# prim_analog_in.net
KiCad netlist of a schematic drawn in Altium Designer
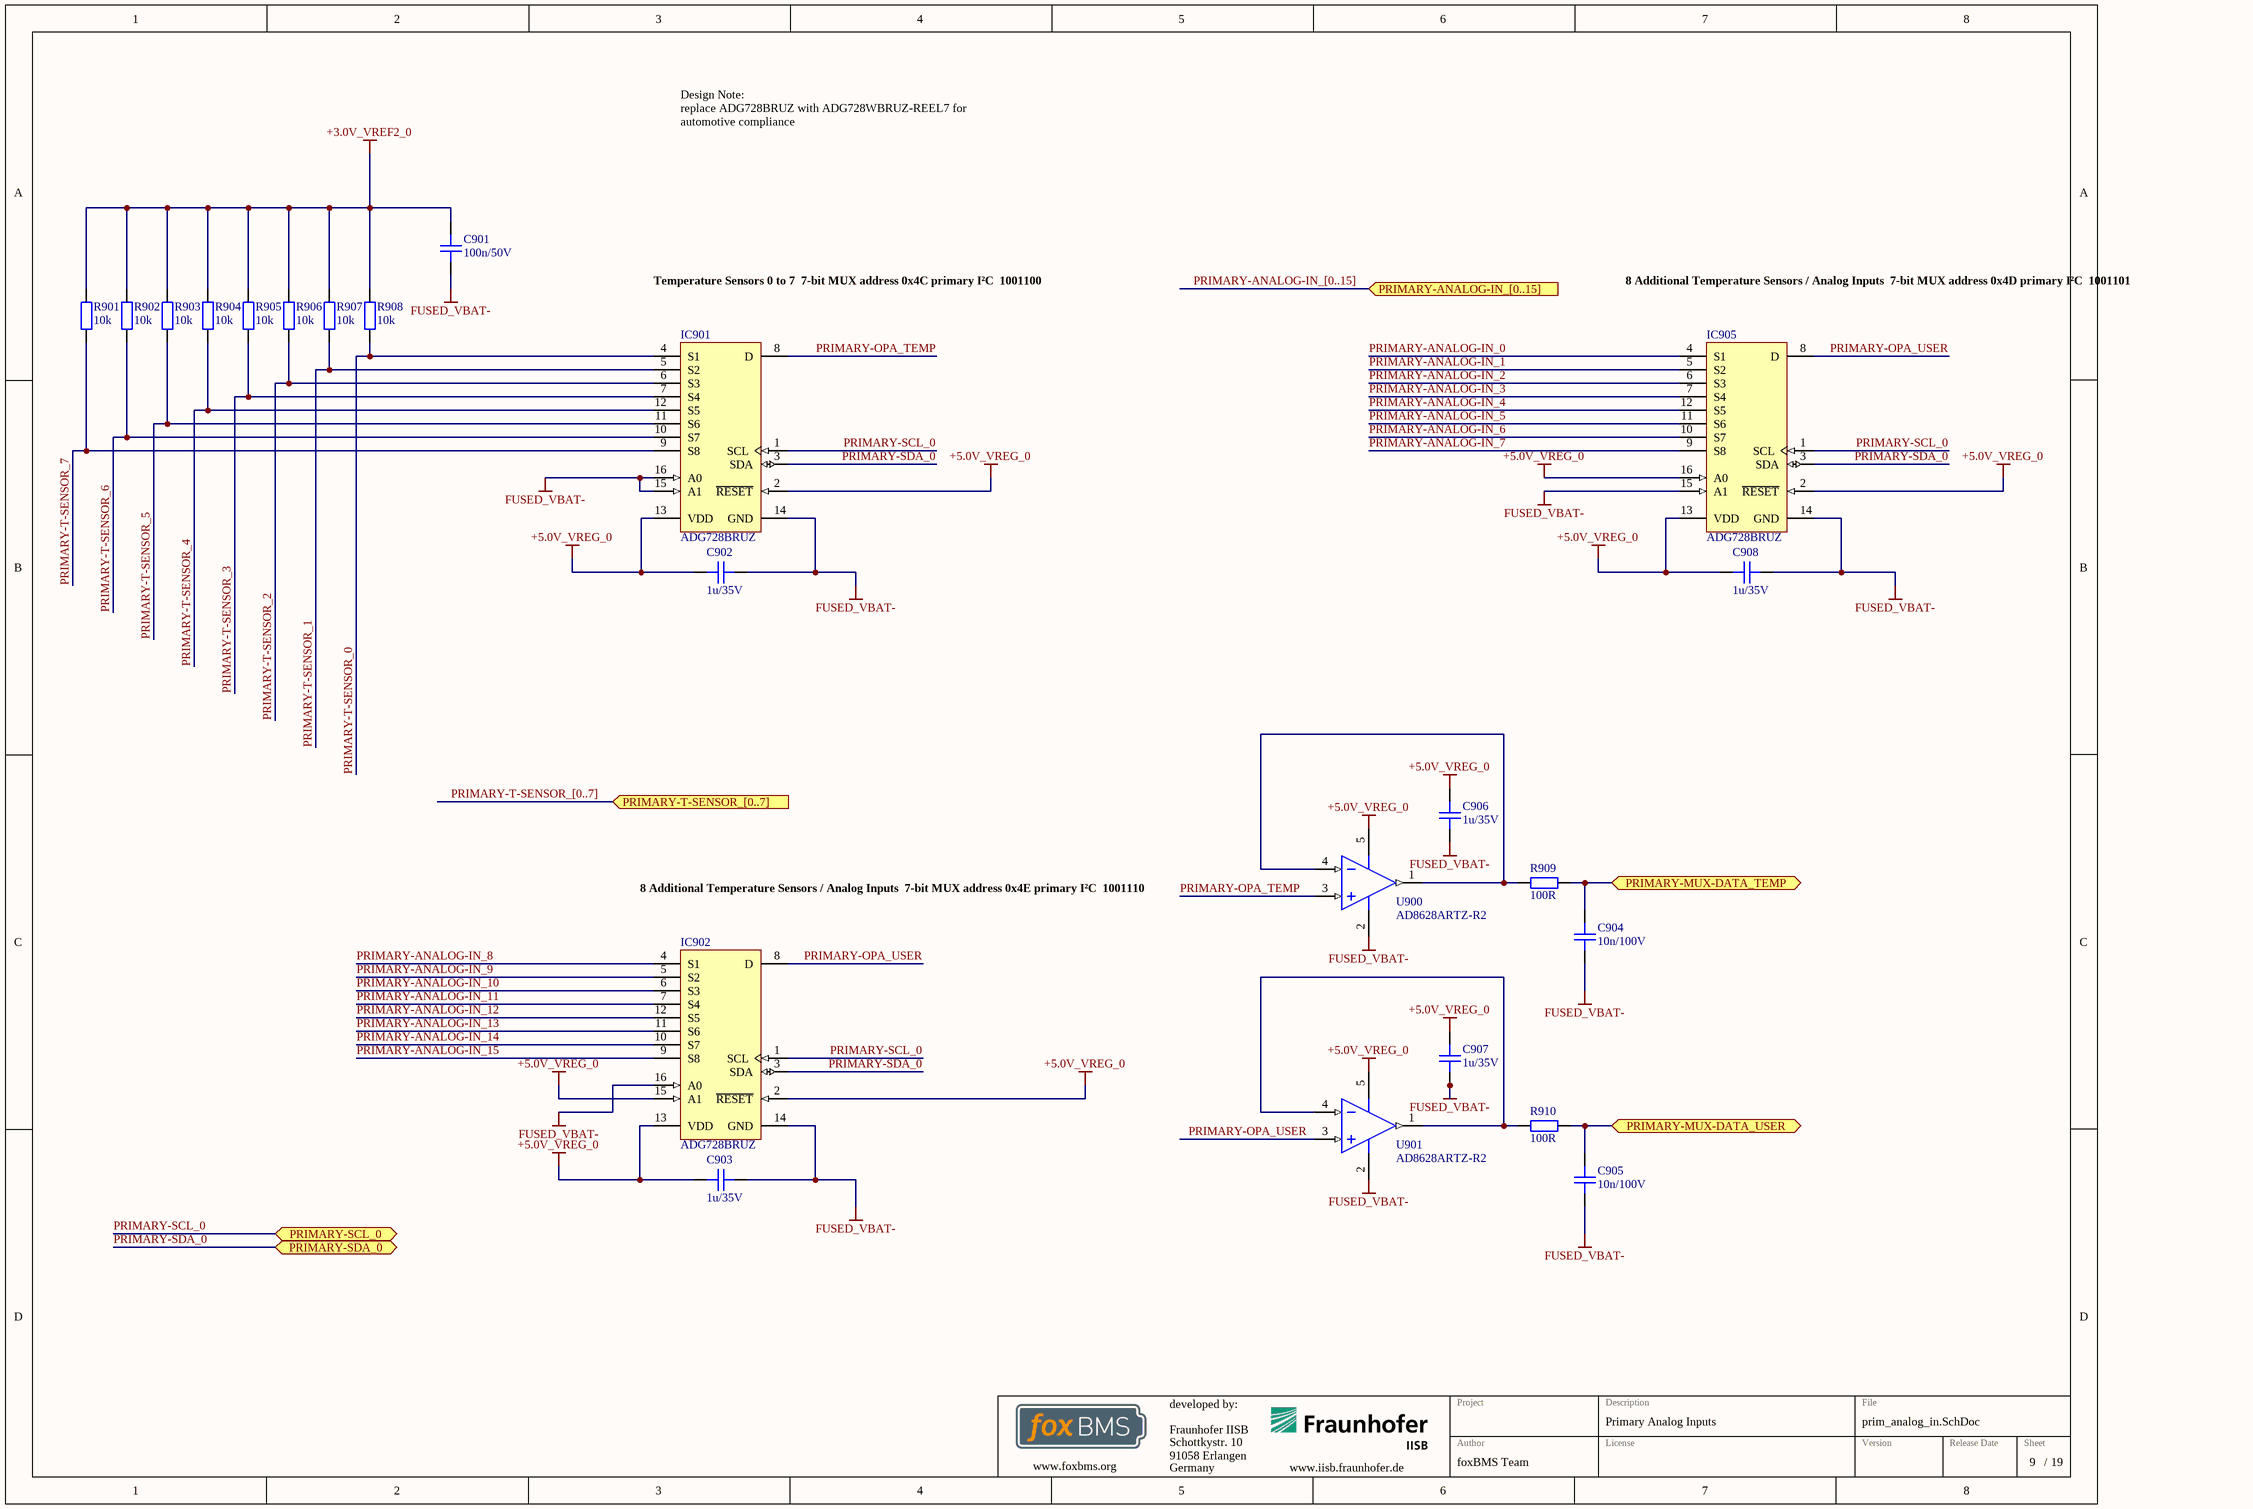
[diagram p0: prim_analog_in.SchDoc]

(export (version "E")
  (design (tool "Eeschema 10.0.6"))
  (components
    (comp (ref "C901")
      (value "100n/50V")
      (footprint "CAPC1608X08N")
      (description "MLCC")
      (fields (field (name "PART NUMBER") "gen_C_ceramic_100n_50V_X7R_0603"))
      (libsource (lib "OE750") (part "C"))
    )
    (comp (ref "C902")
      (value "1u/35V")
      (footprint "CAPC1608X08N")
      (description "MLCC")
      (fields (field (name "PART NUMBER") "gen_C_ceramic_1u_35V_X7R_0603"))
      (libsource (lib "OE750") (part "C"))
    )
    (comp (ref "C903")
      (value "1u/35V")
      (footprint "CAPC1608X08N")
      (description "MLCC")
      (fields (field (name "PART NUMBER") "gen_C_ceramic_1u_35V_X7R_0603"))
      (libsource (lib "OE750") (part "C"))
    )
    (comp (ref "C904")
      (value "10n/100V")
      (footprint "CAPC1608X08N")
      (description "MLCC")
      (fields (field (name "PART NUMBER") "gen_C_ceramic_10n_100V_X7R_0603"))
      (libsource (lib "OE750") (part "C"))
    )
    (comp (ref "C905")
      (value "10n/100V")
      (footprint "CAPC1608X08N")
      (description "MLCC")
      (fields (field (name "PART NUMBER") "gen_C_ceramic_10n_100V_X7R_0603"))
      (libsource (lib "OE750") (part "C"))
    )
    (comp (ref "C906")
      (value "1u/35V")
      (footprint "CAPC1608X08N")
      (description "MLCC")
      (fields (field (name "PART NUMBER") "gen_C_ceramic_1u_35V_X7R_0603"))
      (libsource (lib "OE750") (part "C"))
    )
    (comp (ref "C907")
      (value "1u/35V")
      (footprint "CAPC1608X08N")
      (description "MLCC")
      (fields (field (name "PART NUMBER") "gen_C_ceramic_1u_35V_X7R_0603"))
      (libsource (lib "OE750") (part "C"))
    )
    (comp (ref "C908")
      (value "1u/35V")
      (footprint "CAPC1608X08N")
      (description "MLCC")
      (fields (field (name "PART NUMBER") "gen_C_ceramic_1u_35V_X7R_0603"))
      (libsource (lib "OE750") (part "C"))
    )
    (comp (ref "IC901")
      (value "ADG728BRUZ")
      (footprint "ADI-RU-16_M")
      (fields (field (name "MANUFACTURER") "Analog Devices"))
      (libsource (lib "Altium Content Vault") (part "ADI-ADG728-RU-16"))
    )
    (comp (ref "IC902")
      (value "ADG728BRUZ")
      (footprint "ADI-RU-16_M")
      (fields (field (name "MANUFACTURER") "Analog Devices"))
      (libsource (lib "Altium Content Vault") (part "ADI-ADG728-RU-16"))
    )
    (comp (ref "IC905")
      (value "ADG728BRUZ")
      (footprint "ADI-RU-16_M")
      (fields (field (name "MANUFACTURER") "Analog Devices"))
      (libsource (lib "Altium Content Vault") (part "ADI-ADG728-RU-16"))
    )
    (comp (ref "R901")
      (value "10k")
      (footprint "RESC1608X05N")
      (description "SMD Resistor 10k 0603")
      (fields (field (name "PART NUMBER") "gen_R_10k_0603") (field (name "TOLERANCE") "1%"))
      (libsource (lib "OE750") (part "R"))
    )
    (comp (ref "R902")
      (value "10k")
      (footprint "RESC1608X05N")
      (description "SMD Resistor 10k 0603")
      (fields (field (name "PART NUMBER") "gen_R_10k_0603") (field (name "TOLERANCE") "1%"))
      (libsource (lib "OE750") (part "R"))
    )
    (comp (ref "R903")
      (value "10k")
      (footprint "RESC1608X05N")
      (description "SMD Resistor 10k 0603")
      (fields (field (name "PART NUMBER") "gen_R_10k_0603") (field (name "TOLERANCE") "1%"))
      (libsource (lib "OE750") (part "R"))
    )
    (comp (ref "R904")
      (value "10k")
      (footprint "RESC1608X05N")
      (description "SMD Resistor 10k 0603")
      (fields (field (name "PART NUMBER") "gen_R_10k_0603") (field (name "TOLERANCE") "1%"))
      (libsource (lib "OE750") (part "R"))
    )
    (comp (ref "R905")
      (value "10k")
      (footprint "RESC1608X05N")
      (description "SMD Resistor 10k 0603")
      (fields (field (name "PART NUMBER") "gen_R_10k_0603") (field (name "TOLERANCE") "1%"))
      (libsource (lib "OE750") (part "R"))
    )
    (comp (ref "R906")
      (value "10k")
      (footprint "RESC1608X05N")
      (description "SMD Resistor 10k 0603")
      (fields (field (name "PART NUMBER") "gen_R_10k_0603") (field (name "TOLERANCE") "1%"))
      (libsource (lib "OE750") (part "R"))
    )
    (comp (ref "R907")
      (value "10k")
      (footprint "RESC1608X05N")
      (description "SMD Resistor 10k 0603")
      (fields (field (name "PART NUMBER") "gen_R_10k_0603") (field (name "TOLERANCE") "1%"))
      (libsource (lib "OE750") (part "R"))
    )
    (comp (ref "R908")
      (value "10k")
      (footprint "RESC1608X05N")
      (description "SMD Resistor 10k 0603")
      (fields (field (name "PART NUMBER") "gen_R_10k_0603") (field (name "TOLERANCE") "1%"))
      (libsource (lib "OE750") (part "R"))
    )
    (comp (ref "R909")
      (value "100R")
      (footprint "RESC1608X05N")
      (description "SMD Resistor 100R 0603")
      (fields (field (name "PART NUMBER") "gen_R_100R_0603") (field (name "TOLERANCE") "1%"))
      (libsource (lib "OE750") (part "R"))
    )
    (comp (ref "R910")
      (value "100R")
      (footprint "RESC1608X05N")
      (description "SMD Resistor 100R 0603")
      (fields (field (name "PART NUMBER") "gen_R_100R_0603") (field (name "TOLERANCE") "1%"))
      (libsource (lib "OE750") (part "R"))
    )
    (comp (ref "U900")
      (value "AD8628ARTZ-R2")
      (footprint "ADI-RJ-5_M")
      (fields (field (name "MANUFACTURER") "Analog Devices") (field (name "GENERIC PART NUMBER") "AD8628"))
      (libsource (lib "Altium Content Vault") (part "ADI-ADxxxx-X-5"))
    )
    (comp (ref "U901")
      (value "AD8628ARTZ-R2")
      (footprint "ADI-RJ-5_M")
      (fields (field (name "MANUFACTURER") "Analog Devices") (field (name "GENERIC PART NUMBER") "AD8628"))
      (libsource (lib "Altium Content Vault") (part "ADI-ADxxxx-X-5"))
    )
  )
  (nets
    (net (code "1") (name "+3.0V_VREF2_0") (class "Default")
      (node (ref "C901") (pin "2") (pinfunction "2_2") (pintype "passive"))
      (node (ref "R901") (pin "2") (pinfunction "2_2") (pintype "passive"))
      (node (ref "R902") (pin "2") (pinfunction "2_2") (pintype "passive"))
      (node (ref "R903") (pin "2") (pinfunction "2_2") (pintype "passive"))
      (node (ref "R904") (pin "2") (pinfunction "2_2") (pintype "passive"))
      (node (ref "R905") (pin "2") (pinfunction "2_2") (pintype "passive"))
      (node (ref "R906") (pin "2") (pinfunction "2_2") (pintype "passive"))
      (node (ref "R907") (pin "2") (pinfunction "2_2") (pintype "passive"))
      (node (ref "R908") (pin "2") (pinfunction "2_2") (pintype "passive"))
    )
    (net (code "2") (name "+5.0V_VREG_0") (class "Default")
      (node (ref "C902") (pin "2") (pinfunction "2_2") (pintype "passive"))
      (node (ref "C903") (pin "2") (pinfunction "2_2") (pintype "passive"))
      (node (ref "C906") (pin "2") (pinfunction "2_2") (pintype "passive"))
      (node (ref "C907") (pin "2") (pinfunction "2_2") (pintype "passive"))
      (node (ref "C908") (pin "2") (pinfunction "2_2") (pintype "passive"))
      (node (ref "IC901") (pin "13") (pinfunction "VDD_13") (pintype "power_in"))
      (node (ref "IC901") (pin "2") (pinfunction "~{RESET}_2") (pintype "input"))
      (node (ref "IC902") (pin "13") (pinfunction "VDD_13") (pintype "power_in"))
      (node (ref "IC902") (pin "15") (pinfunction "A1_15") (pintype "input"))
      (node (ref "IC902") (pin "2") (pinfunction "~{RESET}_2") (pintype "input"))
      (node (ref "IC905") (pin "13") (pinfunction "VDD_13") (pintype "power_in"))
      (node (ref "IC905") (pin "16") (pinfunction "A0_16") (pintype "input"))
      (node (ref "IC905") (pin "2") (pinfunction "~{RESET}_2") (pintype "input"))
      (node (ref "U900") (pin "5") (pinfunction "+V_5") (pintype "power_in"))
      (node (ref "U901") (pin "5") (pinfunction "+V_5") (pintype "power_in"))
    )
    (net (code "3") (name "/PRIMARY-ANALOG-IN_0") (class "Default")
      (node (ref "IC905") (pin "4") (pinfunction "S1_4") (pintype "passive"))
    )
    (net (code "4") (name "/PRIMARY-ANALOG-IN_1") (class "Default")
      (node (ref "IC905") (pin "5") (pinfunction "S2_5") (pintype "passive"))
    )
    (net (code "5") (name "/PRIMARY-ANALOG-IN_2") (class "Default")
      (node (ref "IC905") (pin "6") (pinfunction "S3_6") (pintype "passive"))
    )
    (net (code "6") (name "/PRIMARY-ANALOG-IN_3") (class "Default")
      (node (ref "IC905") (pin "7") (pinfunction "S4_7") (pintype "passive"))
    )
    (net (code "7") (name "/PRIMARY-ANALOG-IN_4") (class "Default")
      (node (ref "IC905") (pin "12") (pinfunction "S5_12") (pintype "passive"))
    )
    (net (code "8") (name "/PRIMARY-ANALOG-IN_5") (class "Default")
      (node (ref "IC905") (pin "11") (pinfunction "S6_11") (pintype "passive"))
    )
    (net (code "9") (name "/PRIMARY-ANALOG-IN_6") (class "Default")
      (node (ref "IC905") (pin "10") (pinfunction "S7_10") (pintype "passive"))
    )
    (net (code "10") (name "/PRIMARY-ANALOG-IN_7") (class "Default")
      (node (ref "IC905") (pin "9") (pinfunction "S8_9") (pintype "passive"))
    )
    (net (code "11") (name "/PRIMARY-ANALOG-IN_8") (class "Default")
      (node (ref "IC902") (pin "4") (pinfunction "S1_4") (pintype "passive"))
    )
    (net (code "12") (name "/PRIMARY-ANALOG-IN_9") (class "Default")
      (node (ref "IC902") (pin "5") (pinfunction "S2_5") (pintype "passive"))
    )
    (net (code "13") (name "/PRIMARY-ANALOG-IN_10") (class "Default")
      (node (ref "IC902") (pin "6") (pinfunction "S3_6") (pintype "passive"))
    )
    (net (code "14") (name "/PRIMARY-ANALOG-IN_11") (class "Default")
      (node (ref "IC902") (pin "7") (pinfunction "S4_7") (pintype "passive"))
    )
    (net (code "15") (name "/PRIMARY-ANALOG-IN_12") (class "Default")
      (node (ref "IC902") (pin "12") (pinfunction "S5_12") (pintype "passive"))
    )
    (net (code "16") (name "/PRIMARY-ANALOG-IN_13") (class "Default")
      (node (ref "IC902") (pin "11") (pinfunction "S6_11") (pintype "passive"))
    )
    (net (code "17") (name "/PRIMARY-ANALOG-IN_14") (class "Default")
      (node (ref "IC902") (pin "10") (pinfunction "S7_10") (pintype "passive"))
    )
    (net (code "18") (name "/PRIMARY-ANALOG-IN_15") (class "Default")
      (node (ref "IC902") (pin "9") (pinfunction "S8_9") (pintype "passive"))
    )
    (net (code "20") (name "/PRIMARY-MUX-DATA_TEMP") (class "Default")
      (node (ref "C904") (pin "2") (pinfunction "2_2") (pintype "passive"))
      (node (ref "R909") (pin "2") (pinfunction "2_2") (pintype "passive"))
    )
    (net (code "21") (name "/PRIMARY-MUX-DATA_USER") (class "Default")
      (node (ref "C905") (pin "2") (pinfunction "2_2") (pintype "passive"))
      (node (ref "R910") (pin "2") (pinfunction "2_2") (pintype "passive"))
    )
    (net (code "22") (name "/PRIMARY-OPA_TEMP") (class "Default")
      (node (ref "IC901") (pin "8") (pinfunction "D_8") (pintype "passive"))
      (node (ref "U900") (pin "3") (pinfunction "+IN_3") (pintype "input"))
    )
    (net (code "23") (name "/PRIMARY-OPA_USER") (class "Default")
      (node (ref "IC902") (pin "8") (pinfunction "D_8") (pintype "passive"))
      (node (ref "IC905") (pin "8") (pinfunction "D_8") (pintype "passive"))
      (node (ref "U901") (pin "3") (pinfunction "+IN_3") (pintype "input"))
    )
    (net (code "24") (name "/PRIMARY-SCL_0") (class "Default")
      (node (ref "IC901") (pin "1") (pinfunction "SCL_1") (pintype "input"))
      (node (ref "IC902") (pin "1") (pinfunction "SCL_1") (pintype "input"))
      (node (ref "IC905") (pin "1") (pinfunction "SCL_1") (pintype "input"))
    )
    (net (code "25") (name "/PRIMARY-SDA_0") (class "Default")
      (node (ref "IC901") (pin "3") (pinfunction "SDA_3") (pintype "bidirectional"))
      (node (ref "IC902") (pin "3") (pinfunction "SDA_3") (pintype "bidirectional"))
      (node (ref "IC905") (pin "3") (pinfunction "SDA_3") (pintype "bidirectional"))
    )
    (net (code "26") (name "/PRIMARY-T-SENSOR_0") (class "Default")
      (node (ref "IC901") (pin "4") (pinfunction "S1_4") (pintype "passive"))
      (node (ref "R908") (pin "1") (pinfunction "1_1") (pintype "passive"))
    )
    (net (code "27") (name "/PRIMARY-T-SENSOR_1") (class "Default")
      (node (ref "IC901") (pin "5") (pinfunction "S2_5") (pintype "passive"))
      (node (ref "R907") (pin "1") (pinfunction "1_1") (pintype "passive"))
    )
    (net (code "28") (name "/PRIMARY-T-SENSOR_2") (class "Default")
      (node (ref "IC901") (pin "6") (pinfunction "S3_6") (pintype "passive"))
      (node (ref "R906") (pin "1") (pinfunction "1_1") (pintype "passive"))
    )
    (net (code "29") (name "/PRIMARY-T-SENSOR_3") (class "Default")
      (node (ref "IC901") (pin "7") (pinfunction "S4_7") (pintype "passive"))
      (node (ref "R905") (pin "1") (pinfunction "1_1") (pintype "passive"))
    )
    (net (code "30") (name "/PRIMARY-T-SENSOR_4") (class "Default")
      (node (ref "IC901") (pin "12") (pinfunction "S5_12") (pintype "passive"))
      (node (ref "R904") (pin "1") (pinfunction "1_1") (pintype "passive"))
    )
    (net (code "31") (name "/PRIMARY-T-SENSOR_5") (class "Default")
      (node (ref "IC901") (pin "11") (pinfunction "S6_11") (pintype "passive"))
      (node (ref "R903") (pin "1") (pinfunction "1_1") (pintype "passive"))
    )
    (net (code "32") (name "/PRIMARY-T-SENSOR_6") (class "Default")
      (node (ref "IC901") (pin "10") (pinfunction "S7_10") (pintype "passive"))
      (node (ref "R902") (pin "1") (pinfunction "1_1") (pintype "passive"))
    )
    (net (code "33") (name "/PRIMARY-T-SENSOR_7") (class "Default")
      (node (ref "IC901") (pin "9") (pinfunction "S8_9") (pintype "passive"))
      (node (ref "R901") (pin "1") (pinfunction "1_1") (pintype "passive"))
    )
    (net (code "35") (name "FUSED_VBAT-") (class "Default")
      (node (ref "C901") (pin "1") (pinfunction "1_1") (pintype "passive"))
      (node (ref "C902") (pin "1") (pinfunction "1_1") (pintype "passive"))
      (node (ref "C903") (pin "1") (pinfunction "1_1") (pintype "passive"))
      (node (ref "C904") (pin "1") (pinfunction "1_1") (pintype "passive"))
      (node (ref "C905") (pin "1") (pinfunction "1_1") (pintype "passive"))
      (node (ref "C906") (pin "1") (pinfunction "1_1") (pintype "passive"))
      (node (ref "C907") (pin "1") (pinfunction "1_1") (pintype "passive"))
      (node (ref "C908") (pin "1") (pinfunction "1_1") (pintype "passive"))
      (node (ref "IC901") (pin "14") (pinfunction "GND_14") (pintype "power_in"))
      (node (ref "IC901") (pin "15") (pinfunction "A1_15") (pintype "input"))
      (node (ref "IC901") (pin "16") (pinfunction "A0_16") (pintype "input"))
      (node (ref "IC902") (pin "14") (pinfunction "GND_14") (pintype "power_in"))
      (node (ref "IC902") (pin "16") (pinfunction "A0_16") (pintype "input"))
      (node (ref "IC905") (pin "14") (pinfunction "GND_14") (pintype "power_in"))
      (node (ref "IC905") (pin "15") (pinfunction "A1_15") (pintype "input"))
      (node (ref "U900") (pin "2") (pinfunction "-V_2") (pintype "power_in"))
      (node (ref "U901") (pin "2") (pinfunction "-V_2") (pintype "power_in"))
    )
    (net (code "36") (name "Net-(U900--IN)") (class "Default")
      (node (ref "R909") (pin "1") (pinfunction "1_1") (pintype "passive"))
      (node (ref "U900") (pin "1") (pinfunction "OUT_1") (pintype "output"))
      (node (ref "U900") (pin "4") (pinfunction "-IN_4") (pintype "input"))
    )
    (net (code "37") (name "Net-(U901--IN)") (class "Default")
      (node (ref "R910") (pin "1") (pinfunction "1_1") (pintype "passive"))
      (node (ref "U901") (pin "1") (pinfunction "OUT_1") (pintype "output"))
      (node (ref "U901") (pin "4") (pinfunction "-IN_4") (pintype "input"))
    )
  )
)
